# Mouse_STM32F401_DB9_v1_1.net
KiCad netlist of a schematic drawn in EAGLE
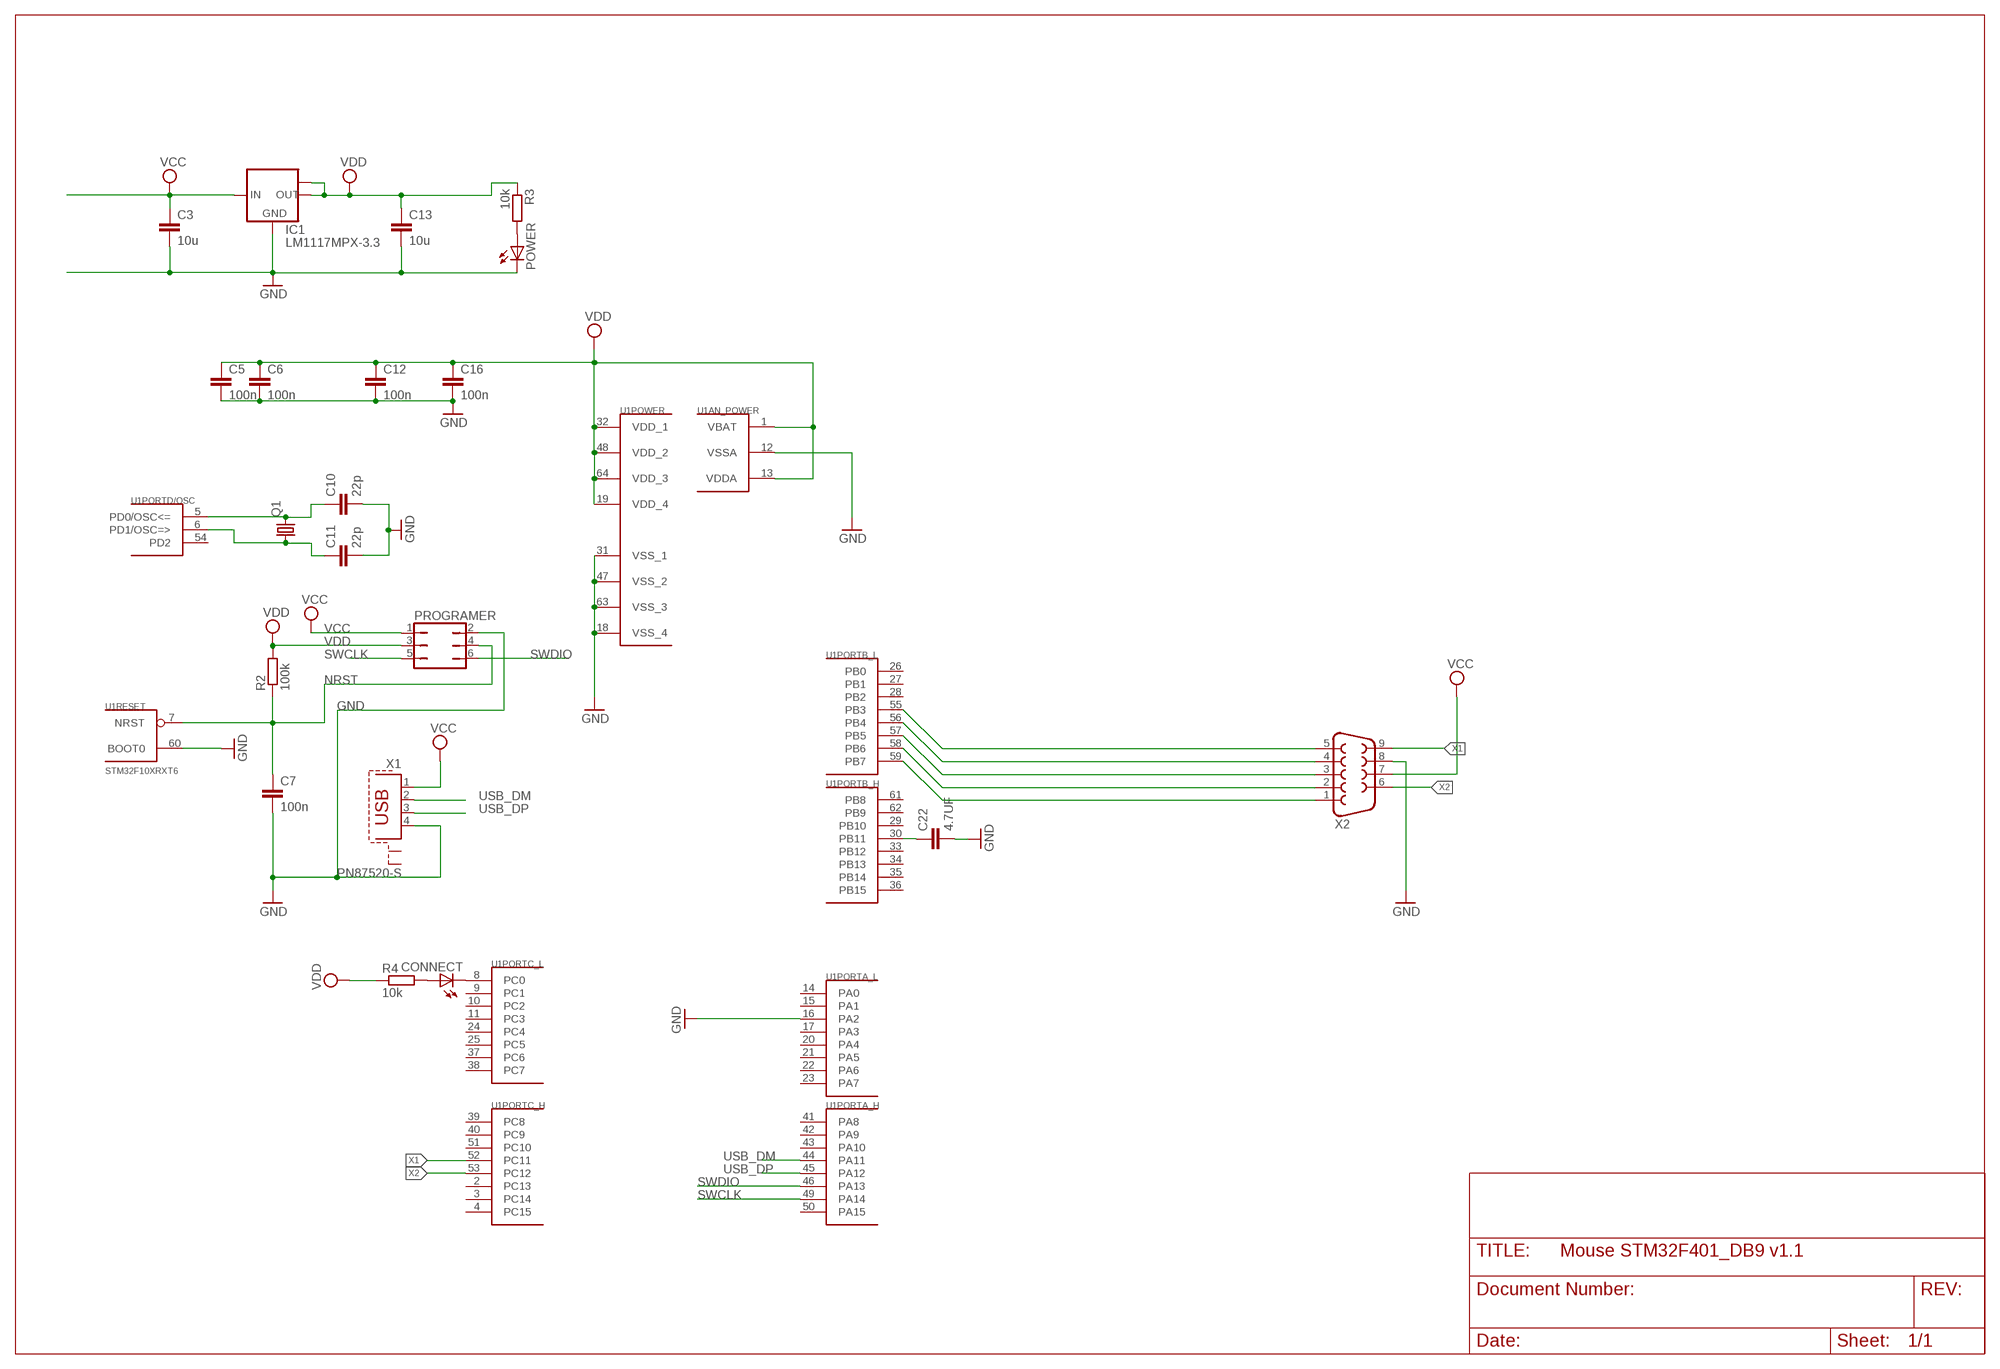
[diagram p0: schematic, sheet 1]

(export (version "E")
  (design (tool "Eeschema 10.0.6"))
  (components
    (comp (ref "C3")
      (value "10u")
      (footprint "eagle-import:C1206")
      (libsource (lib "eagle-import") (part "C-EUC1206"))
    )
    (comp (ref "C5")
      (value "100n")
      (footprint "eagle-import:C0603")
      (libsource (lib "eagle-import") (part "C-EUC0603"))
    )
    (comp (ref "C6")
      (value "100n")
      (footprint "eagle-import:C0603")
      (libsource (lib "eagle-import") (part "C-EUC0603"))
    )
    (comp (ref "C7")
      (value "100n")
      (footprint "eagle-import:C0603")
      (libsource (lib "eagle-import") (part "C-EUC0603"))
    )
    (comp (ref "C10")
      (value "22p")
      (footprint "eagle-import:C0603")
      (libsource (lib "eagle-import") (part "C-EUC0603"))
    )
    (comp (ref "C11")
      (value "22p")
      (footprint "eagle-import:C0603")
      (libsource (lib "eagle-import") (part "C-EUC0603"))
    )
    (comp (ref "C12")
      (value "100n")
      (footprint "eagle-import:C0603")
      (libsource (lib "eagle-import") (part "C-EUC0603"))
    )
    (comp (ref "C13")
      (value "10u")
      (footprint "eagle-import:C1206")
      (libsource (lib "eagle-import") (part "C-EUC1206"))
    )
    (comp (ref "C16")
      (value "100n")
      (footprint "eagle-import:C0603")
      (libsource (lib "eagle-import") (part "C-EUC0603"))
    )
    (comp (ref "C22")
      (value "4.7UF")
      (footprint "eagle-import:C1206")
      (libsource (lib "eagle-import") (part "C-EUC1206"))
    )
    (comp (ref "CONNECT")
      (value "LEDSML0805")
      (footprint "eagle-import:SML0805")
      (libsource (lib "eagle-import") (part "LEDSML0805"))
    )
    (comp (ref "IC1")
      (value "LM1117MPX-3.3")
      (footprint "eagle-import:SOT223")
      (libsource (lib "eagle-import") (part "LM1117MPX-3.3"))
    )
    (comp (ref "POWER")
      (value "LEDSML0805")
      (footprint "eagle-import:SML0805")
      (libsource (lib "eagle-import") (part "LEDSML0805"))
    )
    (comp (ref "PROGRAMER")
      (value "JP3Q")
      (footprint "eagle-import:JP3Q")
      (libsource (lib "eagle-import") (part "JP3Q"))
    )
    (comp (ref "Q1")
      (value "CRYSTALHC49S")
      (footprint "eagle-import:HC49_S")
      (libsource (lib "eagle-import") (part "CRYSTALHC49S"))
    )
    (comp (ref "R2")
      (value "100k")
      (footprint "eagle-import:R0603")
      (libsource (lib "eagle-import") (part "R-EU_R0603"))
    )
    (comp (ref "R3")
      (value "10k")
      (footprint "eagle-import:R0603")
      (libsource (lib "eagle-import") (part "R-EU_R0603"))
    )
    (comp (ref "R4")
      (value "10k")
      (footprint "eagle-import:R0603")
      (libsource (lib "eagle-import") (part "R-EU_R0603"))
    )
    (comp (ref "U1")
      (value "STM32F10XRXT6")
      (footprint "eagle-import:TQFP64")
      (libsource (lib "eagle-import") (part "STM32F10XRXT6"))
    )
    (comp (ref "X1")
      (value "PN87520-S")
      (footprint "eagle-import:PN87520-S")
      (libsource (lib "eagle-import") (part "PN87520-S"))
    )
    (comp (ref "X2")
      (value "F09HP")
      (footprint "eagle-import:F09HP")
      (libsource (lib "eagle-import") (part "F09HP"))
    )
  )
  (nets
    (net (code "1") (name "/NRST") (class "Default")
      (node (ref "C7") (pin "1") (pinfunction "1_1") (pintype "passive"))
      (node (ref "PROGRAMER") (pin "4") (pinfunction "4_4") (pintype "passive"))
      (node (ref "R2") (pin "1") (pinfunction "1_1") (pintype "passive"))
      (node (ref "U1") (pin "7") (pinfunction "NRST_7") (pintype "input"))
    )
    (net (code "2") (name "/SWCLK") (class "Default")
      (node (ref "PROGRAMER") (pin "5") (pinfunction "5_5") (pintype "passive"))
      (node (ref "U1") (pin "49") (pinfunction "PA14_49") (pintype "bidirectional"))
    )
    (net (code "3") (name "/SWDIO") (class "Default")
      (node (ref "PROGRAMER") (pin "6") (pinfunction "6_6") (pintype "passive"))
      (node (ref "U1") (pin "46") (pinfunction "PA13_46") (pintype "bidirectional"))
    )
    (net (code "4") (name "/USB_DM") (class "Default")
      (node (ref "U1") (pin "44") (pinfunction "PA11_44") (pintype "bidirectional"))
      (node (ref "X1") (pin "2") (pinfunction "2_2") (pintype "passive"))
    )
    (net (code "5") (name "/USB_DP") (class "Default")
      (node (ref "U1") (pin "45") (pinfunction "PA12_45") (pintype "bidirectional"))
      (node (ref "X1") (pin "3") (pinfunction "3_3") (pintype "passive"))
    )
    (net (code "6") (name "GND") (class "Default")
      (node (ref "C10") (pin "2") (pinfunction "2_2") (pintype "passive"))
      (node (ref "C11") (pin "2") (pinfunction "2_2") (pintype "passive"))
      (node (ref "C12") (pin "2") (pinfunction "2_2") (pintype "passive"))
      (node (ref "C13") (pin "2") (pinfunction "2_2") (pintype "passive"))
      (node (ref "C16") (pin "2") (pinfunction "2_2") (pintype "passive"))
      (node (ref "C22") (pin "2") (pinfunction "2_2") (pintype "passive"))
      (node (ref "C3") (pin "2") (pinfunction "2_2") (pintype "passive"))
      (node (ref "C5") (pin "2") (pinfunction "2_2") (pintype "passive"))
      (node (ref "C6") (pin "2") (pinfunction "2_2") (pintype "passive"))
      (node (ref "C7") (pin "2") (pinfunction "2_2") (pintype "passive"))
      (node (ref "IC1") (pin "1") (pinfunction "GND_1") (pintype "input"))
      (node (ref "POWER") (pin "C") (pinfunction "C_C") (pintype "passive"))
      (node (ref "PROGRAMER") (pin "2") (pinfunction "2_2") (pintype "passive"))
      (node (ref "U1") (pin "12") (pinfunction "VSSA_12") (pintype "power_in"))
      (node (ref "U1") (pin "16") (pinfunction "PA2_16") (pintype "bidirectional"))
      (node (ref "U1") (pin "18") (pinfunction "VSS_4_18") (pintype "power_in"))
      (node (ref "U1") (pin "31") (pinfunction "VSS_1_31") (pintype "power_in"))
      (node (ref "U1") (pin "47") (pinfunction "VSS_2_47") (pintype "power_in"))
      (node (ref "U1") (pin "60") (pinfunction "BOOT0_60") (pintype "input"))
      (node (ref "U1") (pin "63") (pinfunction "VSS_3_63") (pintype "power_in"))
      (node (ref "X1") (pin "4") (pinfunction "4_4") (pintype "passive"))
      (node (ref "X2") (pin "8") (pinfunction "8_8") (pintype "passive"))
    )
    (net (code "7") (name "Net-(CONNECT-PadA)") (class "Default")
      (node (ref "CONNECT") (pin "A") (pinfunction "A_A") (pintype "passive"))
      (node (ref "R4") (pin "2") (pinfunction "2_2") (pintype "passive"))
    )
    (net (code "8") (name "Net-(POWER-PadA)") (class "Default")
      (node (ref "POWER") (pin "A") (pinfunction "A_A") (pintype "passive"))
      (node (ref "R3") (pin "2") (pinfunction "2_2") (pintype "passive"))
    )
    (net (code "9") (name "Net-(U1D-PB11)") (class "Default")
      (node (ref "C22") (pin "1") (pinfunction "1_1") (pintype "passive"))
      (node (ref "U1") (pin "30") (pinfunction "PB11_30") (pintype "bidirectional"))
    )
    (net (code "10") (name "Net-(U1E-PB3)") (class "Default")
      (node (ref "U1") (pin "55") (pinfunction "PB3_55") (pintype "bidirectional"))
      (node (ref "X2") (pin "5") (pinfunction "5_5") (pintype "passive"))
    )
    (net (code "11") (name "Net-(U1E-PB4)") (class "Default")
      (node (ref "U1") (pin "56") (pinfunction "PB4_56") (pintype "bidirectional"))
      (node (ref "X2") (pin "4") (pinfunction "4_4") (pintype "passive"))
    )
    (net (code "12") (name "Net-(U1E-PB5)") (class "Default")
      (node (ref "U1") (pin "57") (pinfunction "PB5_57") (pintype "bidirectional"))
      (node (ref "X2") (pin "3") (pinfunction "3_3") (pintype "passive"))
    )
    (net (code "13") (name "Net-(U1E-PB6)") (class "Default")
      (node (ref "U1") (pin "58") (pinfunction "PB6_58") (pintype "bidirectional"))
      (node (ref "X2") (pin "2") (pinfunction "2_2") (pintype "passive"))
    )
    (net (code "14") (name "Net-(U1E-PB7)") (class "Default")
      (node (ref "U1") (pin "59") (pinfunction "PB7_59") (pintype "bidirectional"))
      (node (ref "X2") (pin "1") (pinfunction "1_1") (pintype "passive"))
    )
    (net (code "15") (name "Net-(U1G-PC0)") (class "Default")
      (node (ref "CONNECT") (pin "C") (pinfunction "C_C") (pintype "passive"))
      (node (ref "U1") (pin "8") (pinfunction "PC0_8") (pintype "bidirectional"))
    )
    (net (code "16") (name "Net-(U1H-PD0{slash}OSC<=)") (class "Default")
      (node (ref "C10") (pin "1") (pinfunction "1_1") (pintype "passive"))
      (node (ref "Q1") (pin "2") (pinfunction "2_2") (pintype "passive"))
      (node (ref "U1") (pin "5") (pinfunction "PD0/OSC<=_5") (pintype "bidirectional"))
    )
    (net (code "17") (name "Net-(U1H-PD1{slash}OSC=>)") (class "Default")
      (node (ref "C11") (pin "1") (pinfunction "1_1") (pintype "passive"))
      (node (ref "Q1") (pin "1") (pinfunction "1_1") (pintype "passive"))
      (node (ref "U1") (pin "6") (pinfunction "PD1/OSC=>_6") (pintype "bidirectional"))
    )
    (net (code "18") (name "VCC") (class "Default")
      (node (ref "C3") (pin "1") (pinfunction "1_1") (pintype "passive"))
      (node (ref "IC1") (pin "3") (pinfunction "IN_3") (pintype "input"))
      (node (ref "PROGRAMER") (pin "1") (pinfunction "1_1") (pintype "passive"))
      (node (ref "X1") (pin "1") (pinfunction "1_1") (pintype "passive"))
      (node (ref "X2") (pin "7") (pinfunction "7_7") (pintype "passive"))
    )
    (net (code "19") (name "VDD") (class "Default")
      (node (ref "C12") (pin "1") (pinfunction "1_1") (pintype "passive"))
      (node (ref "C13") (pin "1") (pinfunction "1_1") (pintype "passive"))
      (node (ref "C16") (pin "1") (pinfunction "1_1") (pintype "passive"))
      (node (ref "C5") (pin "1") (pinfunction "1_1") (pintype "passive"))
      (node (ref "C6") (pin "1") (pinfunction "1_1") (pintype "passive"))
      (node (ref "IC1") (pin "2") (pinfunction "OUT_2") (pintype "passive"))
      (node (ref "IC1") (pin "TAB") (pinfunction "OUT1_TAB") (pintype "passive"))
      (node (ref "PROGRAMER") (pin "3") (pinfunction "3_3") (pintype "passive"))
      (node (ref "R2") (pin "2") (pinfunction "2_2") (pintype "passive"))
      (node (ref "R3") (pin "1") (pinfunction "1_1") (pintype "passive"))
      (node (ref "R4") (pin "1") (pinfunction "1_1") (pintype "passive"))
      (node (ref "U1") (pin "1") (pinfunction "VBAT_1") (pintype "power_in"))
      (node (ref "U1") (pin "13") (pinfunction "VDDA_13") (pintype "power_in"))
      (node (ref "U1") (pin "19") (pinfunction "VDD_4_19") (pintype "power_in"))
      (node (ref "U1") (pin "32") (pinfunction "VDD_1_32") (pintype "power_in"))
      (node (ref "U1") (pin "48") (pinfunction "VDD_2_48") (pintype "power_in"))
      (node (ref "U1") (pin "64") (pinfunction "VDD_3_64") (pintype "power_in"))
    )
    (net (code "20") (name "X1") (class "Default")
      (node (ref "U1") (pin "52") (pinfunction "PC11_52") (pintype "bidirectional"))
      (node (ref "X2") (pin "9") (pinfunction "9_9") (pintype "passive"))
    )
    (net (code "21") (name "X2") (class "Default")
      (node (ref "U1") (pin "53") (pinfunction "PC12_53") (pintype "bidirectional"))
      (node (ref "X2") (pin "6") (pinfunction "6_6") (pintype "passive"))
    )
    (net (code "22") (name "unconnected-(U1B-PA8-Pad41)") (class "Default")
      (node (ref "U1") (pin "41") (pinfunction "PA8_41") (pintype "bidirectional"))
    )
    (net (code "23") (name "unconnected-(U1B-PA9-Pad42)") (class "Default")
      (node (ref "U1") (pin "42") (pinfunction "PA9_42") (pintype "bidirectional"))
    )
    (net (code "24") (name "unconnected-(U1B-PA10-Pad43)") (class "Default")
      (node (ref "U1") (pin "43") (pinfunction "PA10_43") (pintype "bidirectional"))
    )
    (net (code "25") (name "unconnected-(U1B-PA15-Pad50)") (class "Default")
      (node (ref "U1") (pin "50") (pinfunction "PA15_50") (pintype "bidirectional"))
    )
    (net (code "26") (name "unconnected-(U1C-PA0-Pad14)") (class "Default")
      (node (ref "U1") (pin "14") (pinfunction "PA0_14") (pintype "bidirectional"))
    )
    (net (code "27") (name "unconnected-(U1C-PA1-Pad15)") (class "Default")
      (node (ref "U1") (pin "15") (pinfunction "PA1_15") (pintype "bidirectional"))
    )
    (net (code "28") (name "unconnected-(U1C-PA3-Pad17)") (class "Default")
      (node (ref "U1") (pin "17") (pinfunction "PA3_17") (pintype "bidirectional"))
    )
    (net (code "29") (name "unconnected-(U1C-PA4-Pad20)") (class "Default")
      (node (ref "U1") (pin "20") (pinfunction "PA4_20") (pintype "bidirectional"))
    )
    (net (code "30") (name "unconnected-(U1C-PA5-Pad21)") (class "Default")
      (node (ref "U1") (pin "21") (pinfunction "PA5_21") (pintype "bidirectional"))
    )
    (net (code "31") (name "unconnected-(U1C-PA6-Pad22)") (class "Default")
      (node (ref "U1") (pin "22") (pinfunction "PA6_22") (pintype "bidirectional"))
    )
    (net (code "32") (name "unconnected-(U1C-PA7-Pad23)") (class "Default")
      (node (ref "U1") (pin "23") (pinfunction "PA7_23") (pintype "bidirectional"))
    )
    (net (code "33") (name "unconnected-(U1D-PB8-Pad61)") (class "Default")
      (node (ref "U1") (pin "61") (pinfunction "PB8_61") (pintype "bidirectional"))
    )
    (net (code "34") (name "unconnected-(U1D-PB9-Pad62)") (class "Default")
      (node (ref "U1") (pin "62") (pinfunction "PB9_62") (pintype "bidirectional"))
    )
    (net (code "35") (name "unconnected-(U1D-PB10-Pad29)") (class "Default")
      (node (ref "U1") (pin "29") (pinfunction "PB10_29") (pintype "bidirectional"))
    )
    (net (code "36") (name "unconnected-(U1D-PB12-Pad33)") (class "Default")
      (node (ref "U1") (pin "33") (pinfunction "PB12_33") (pintype "bidirectional"))
    )
    (net (code "37") (name "unconnected-(U1D-PB13-Pad34)") (class "Default")
      (node (ref "U1") (pin "34") (pinfunction "PB13_34") (pintype "bidirectional"))
    )
    (net (code "38") (name "unconnected-(U1D-PB14-Pad35)") (class "Default")
      (node (ref "U1") (pin "35") (pinfunction "PB14_35") (pintype "bidirectional"))
    )
    (net (code "39") (name "unconnected-(U1D-PB15-Pad36)") (class "Default")
      (node (ref "U1") (pin "36") (pinfunction "PB15_36") (pintype "bidirectional"))
    )
    (net (code "40") (name "unconnected-(U1E-PB0-Pad26)") (class "Default")
      (node (ref "U1") (pin "26") (pinfunction "PB0_26") (pintype "bidirectional"))
    )
    (net (code "41") (name "unconnected-(U1E-PB1-Pad27)") (class "Default")
      (node (ref "U1") (pin "27") (pinfunction "PB1_27") (pintype "bidirectional"))
    )
    (net (code "42") (name "unconnected-(U1E-PB2-Pad28)") (class "Default")
      (node (ref "U1") (pin "28") (pinfunction "PB2_28") (pintype "bidirectional"))
    )
    (net (code "43") (name "unconnected-(U1F-PC8-Pad39)") (class "Default")
      (node (ref "U1") (pin "39") (pinfunction "PC8_39") (pintype "bidirectional"))
    )
    (net (code "44") (name "unconnected-(U1F-PC9-Pad40)") (class "Default")
      (node (ref "U1") (pin "40") (pinfunction "PC9_40") (pintype "bidirectional"))
    )
    (net (code "45") (name "unconnected-(U1F-PC10-Pad51)") (class "Default")
      (node (ref "U1") (pin "51") (pinfunction "PC10_51") (pintype "bidirectional"))
    )
    (net (code "46") (name "unconnected-(U1F-PC13-Pad2)") (class "Default")
      (node (ref "U1") (pin "2") (pinfunction "PC13_2") (pintype "bidirectional"))
    )
    (net (code "47") (name "unconnected-(U1F-PC14-Pad3)") (class "Default")
      (node (ref "U1") (pin "3") (pinfunction "PC14_3") (pintype "bidirectional"))
    )
    (net (code "48") (name "unconnected-(U1F-PC15-Pad4)") (class "Default")
      (node (ref "U1") (pin "4") (pinfunction "PC15_4") (pintype "bidirectional"))
    )
    (net (code "49") (name "unconnected-(U1G-PC1-Pad9)") (class "Default")
      (node (ref "U1") (pin "9") (pinfunction "PC1_9") (pintype "bidirectional"))
    )
    (net (code "50") (name "unconnected-(U1G-PC2-Pad10)") (class "Default")
      (node (ref "U1") (pin "10") (pinfunction "PC2_10") (pintype "bidirectional"))
    )
    (net (code "51") (name "unconnected-(U1G-PC3-Pad11)") (class "Default")
      (node (ref "U1") (pin "11") (pinfunction "PC3_11") (pintype "bidirectional"))
    )
    (net (code "52") (name "unconnected-(U1G-PC4-Pad24)") (class "Default")
      (node (ref "U1") (pin "24") (pinfunction "PC4_24") (pintype "bidirectional"))
    )
    (net (code "53") (name "unconnected-(U1G-PC5-Pad25)") (class "Default")
      (node (ref "U1") (pin "25") (pinfunction "PC5_25") (pintype "bidirectional"))
    )
    (net (code "54") (name "unconnected-(U1G-PC6-Pad37)") (class "Default")
      (node (ref "U1") (pin "37") (pinfunction "PC6_37") (pintype "bidirectional"))
    )
    (net (code "55") (name "unconnected-(U1G-PC7-Pad38)") (class "Default")
      (node (ref "U1") (pin "38") (pinfunction "PC7_38") (pintype "bidirectional"))
    )
    (net (code "56") (name "unconnected-(U1H-PD2-Pad54)") (class "Default")
      (node (ref "U1") (pin "54") (pinfunction "PD2_54") (pintype "bidirectional"))
    )
    (net (code "57") (name "unconnected-(X1-PadS1)") (class "Default")
      (node (ref "X1") (pin "S1") (pinfunction "S1_S1") (pintype "passive"))
    )
    (net (code "58") (name "unconnected-(X1-PadS2)") (class "Default")
      (node (ref "X1") (pin "S2") (pinfunction "S2_S2") (pintype "passive"))
    )
  )
)
